# ProPrj___2025-10-18.net
KiCad netlist of a schematic drawn in EasyEDA Pro
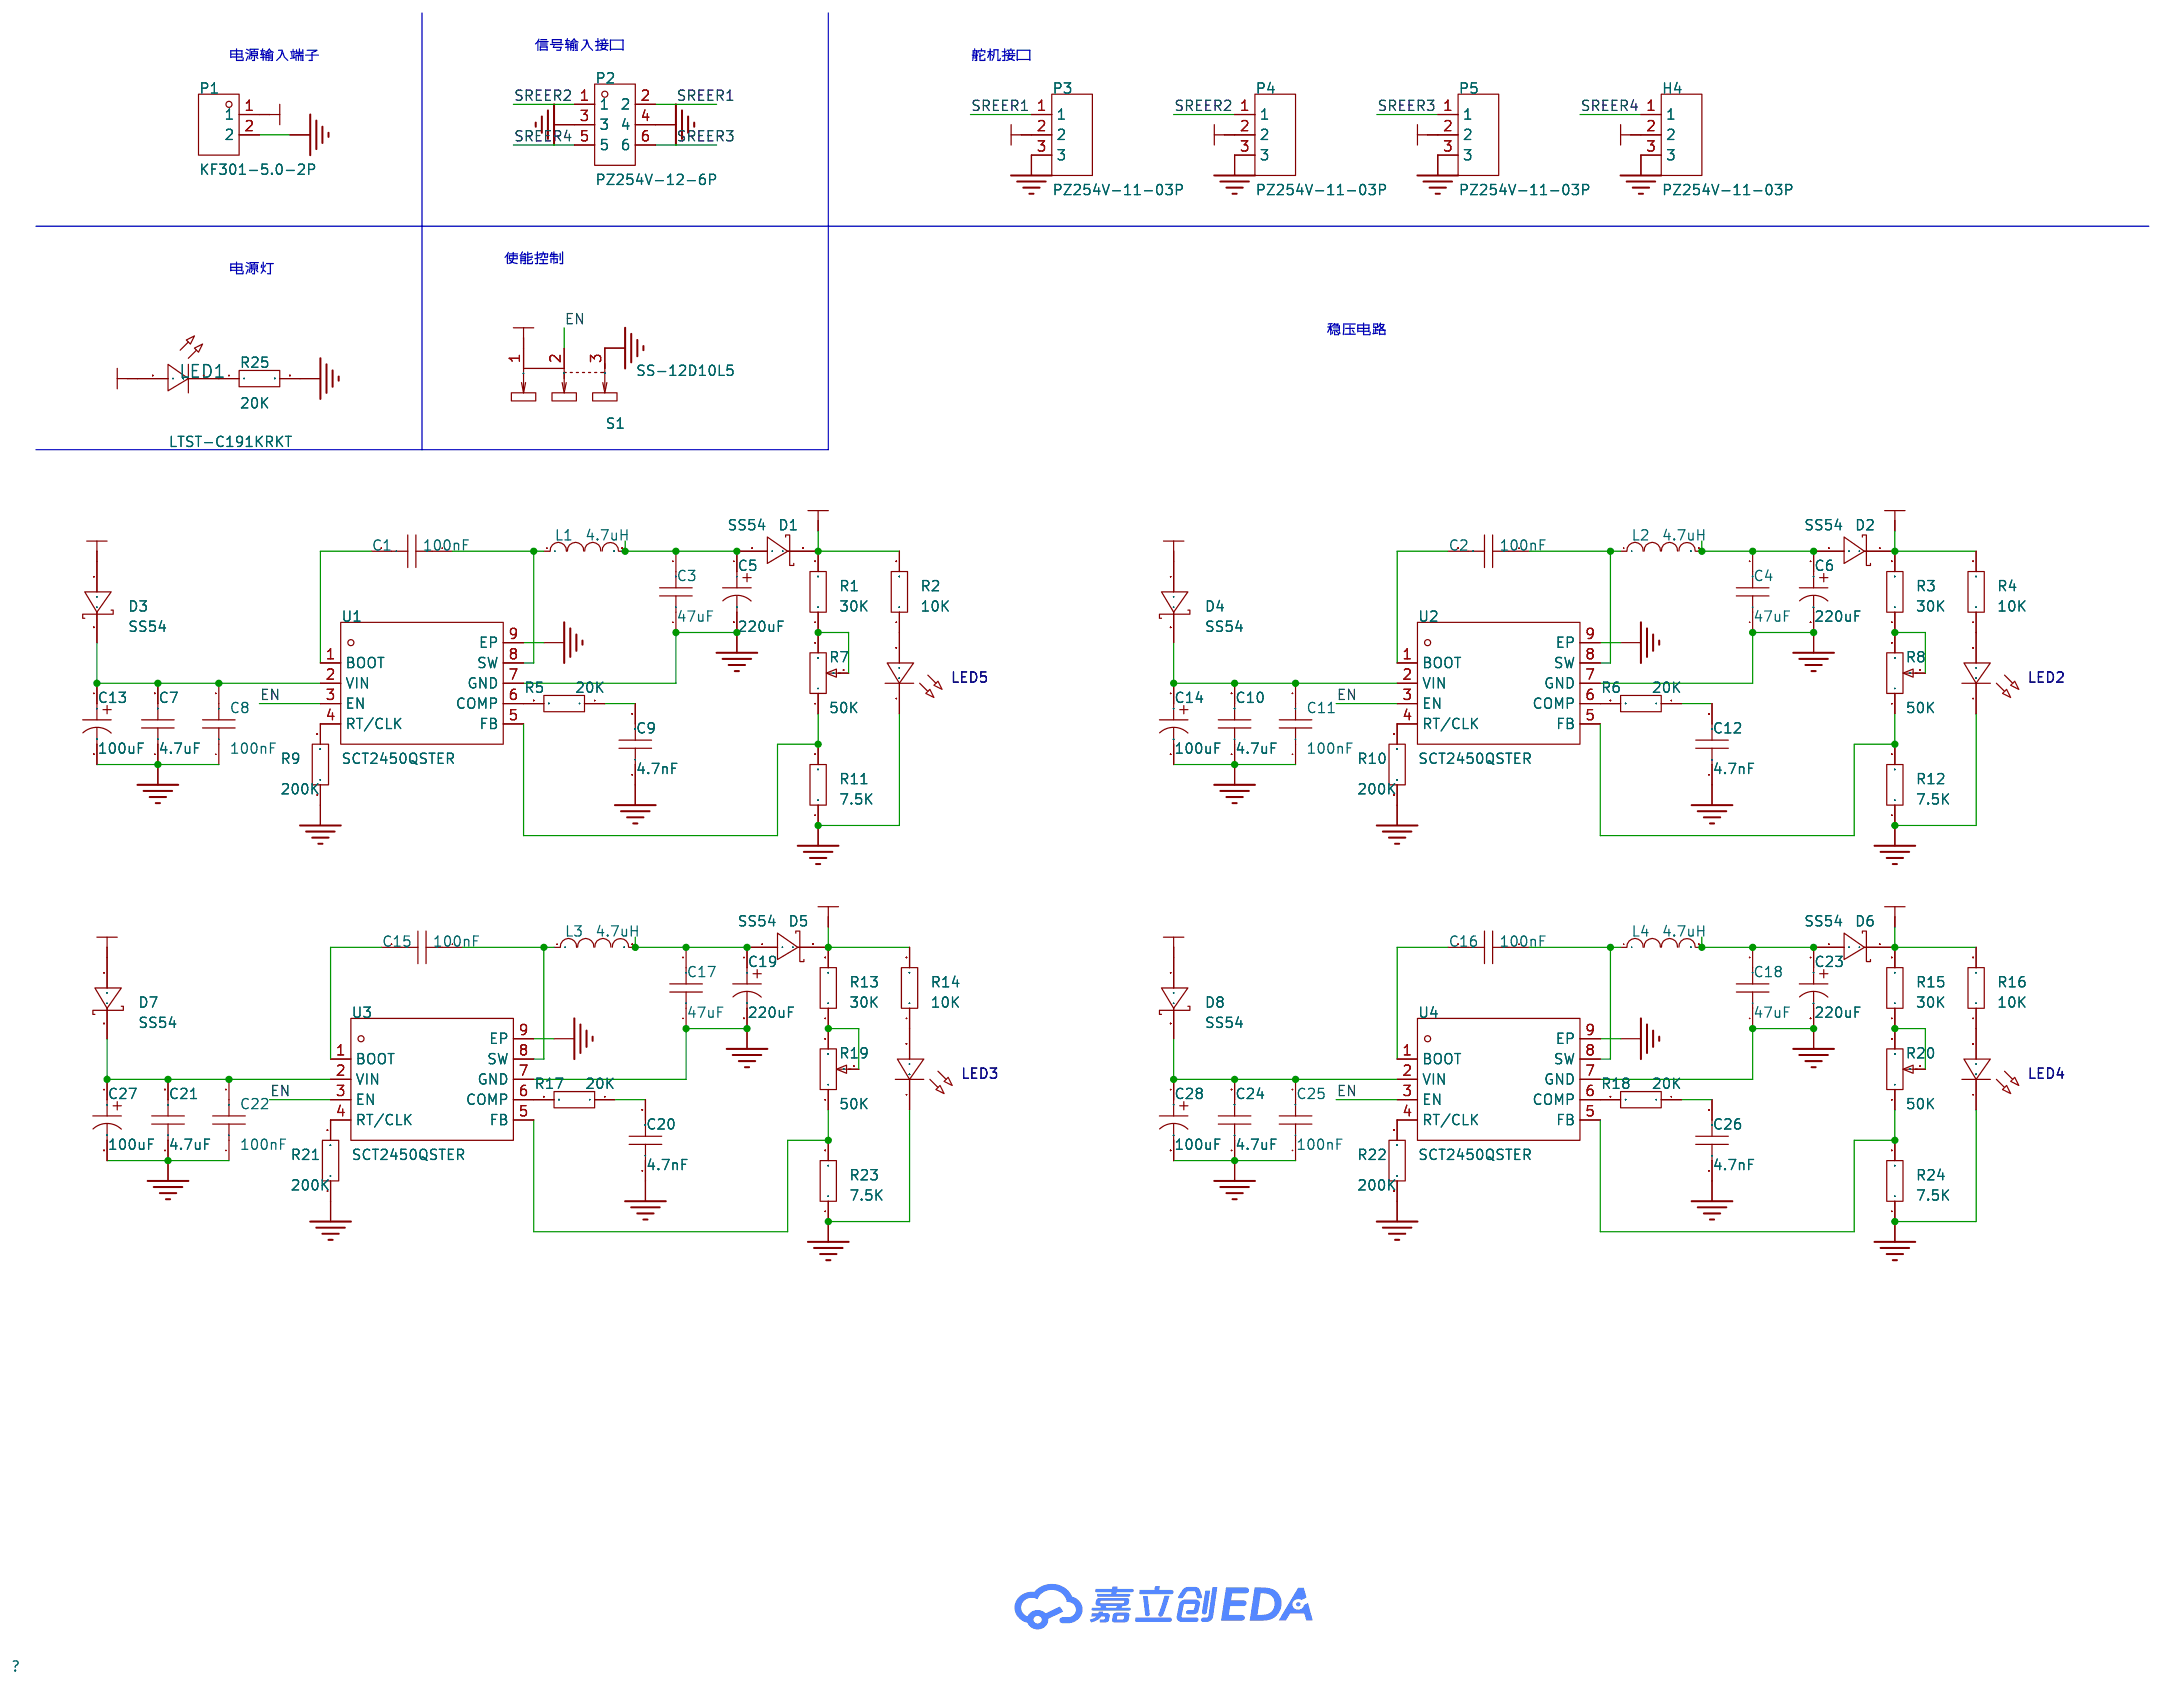
[diagram p0: schematic sheet]

(export (version "E")
  (design (tool "Eeschema 10.0.6"))
  (components
    (comp (ref "C1")
      (value "100nF")
      (footprint "easyedapro:C0603")
      (description "容值:100nF;精度:±10%;额定电压:50V;温度系数:X7R;")
      (fields
        (field (name "Manufacturer Part") "CGA0603X7R104K500JT")
        (field (name "Manufacturer") "HRE(芯声)")
      )
      (libsource (lib "easyedapro") (part "CGA0603X7R104K500JT"))
    )
    (comp (ref "C2")
      (value "100nF")
      (footprint "easyedapro:C0603")
      (description "容值:100nF;精度:±10%;额定电压:50V;温度系数:X7R;")
      (fields
        (field (name "Manufacturer Part") "CGA0603X7R104K500JT")
        (field (name "Manufacturer") "HRE(芯声)")
      )
      (libsource (lib "easyedapro") (part "CGA0603X7R104K500JT"))
    )
    (comp (ref "C3")
      (value "47uF")
      (footprint "easyedapro:C1206")
      (description "容值:47uF;精度:±20%;额定电压:25V;材质(温度系数):X5R;")
      (fields
        (field (name "Manufacturer Part") "HGC1206R5476M250NSPJ")
        (field (name "Manufacturer") "Chinocera(华瓷)")
      )
      (libsource (lib "easyedapro") (part "CGA1206X5R476M250NT"))
    )
    (comp (ref "C4")
      (value "47uF")
      (footprint "easyedapro:C1206")
      (description "容值:47uF;精度:±20%;额定电压:25V;材质(温度系数):X5R;")
      (fields
        (field (name "Manufacturer Part") "HGC1206R5476M250NSPJ")
        (field (name "Manufacturer") "Chinocera(华瓷)")
      )
      (libsource (lib "easyedapro") (part "CGA1206X5R476M250NT"))
    )
    (comp (ref "C5")
      (value "220uF")
      (footprint "easyedapro:CAP-SMD_BD6.3-L6.6-W6.6-LS7.2-FD")
      (description "容值:220uF;精度:±20%;额定电压:16V;纹波电流:110mA@120Hz;等效串联电阻:-;")
      (fields (field (name "Manufacturer Part") "FD1E221M0810") (field (name "Manufacturer") "ChengTao(诚韬)"))
      (libsource (lib "easyedapro") (part "RVT1C221M0607 220UF 16V"))
    )
    (comp (ref "C6")
      (value "220uF")
      (footprint "easyedapro:CAP-SMD_BD6.3-L6.6-W6.6-LS7.2-FD")
      (description "容值:220uF;精度:±20%;额定电压:16V;纹波电流:110mA@120Hz;等效串联电阻:-;")
      (fields (field (name "Manufacturer Part") "FD1E221M0810") (field (name "Manufacturer") "ChengTao(诚韬)"))
      (libsource (lib "easyedapro") (part "RVT1C221M0607 220UF 16V"))
    )
    (comp (ref "C7")
      (value "4.7uF")
      (footprint "easyedapro:C1206")
      (description "容值:4.7uF;精度:±10%;额定电压:35V;材质(温度系数):X5R;")
      (fields
        (field (name "Manufacturer Part") "CL31B475KBHNNNE")
        (field (name "Manufacturer") "SAMSUNG(三星)")
      )
      (libsource (lib "easyedapro") (part "CGA1206X5R475K350NT"))
    )
    (comp (ref "C8")
      (value "100nF")
      (footprint "easyedapro:C0603")
      (description "容值:100nF;精度:±10%;额定电压:50V;温度系数:X7R;")
      (fields
        (field (name "Manufacturer Part") "CGA0603X7R104K500JT")
        (field (name "Manufacturer") "HRE(芯声)")
      )
      (libsource (lib "easyedapro") (part "CGA0603X7R104K500JT"))
    )
    (comp (ref "C9")
      (value "4.7nF")
      (footprint "easyedapro:C0603")
      (description "容值:4.7nF;精度:±10%;额定电压:50V;温度系数:X7R;")
      (fields
        (field (name "Manufacturer Part") "CGA0603X7R472K500JT")
        (field (name "Manufacturer") "HRE(芯声)")
      )
      (libsource (lib "easyedapro") (part "CGA0603X7R472K500JT"))
    )
    (comp (ref "C10")
      (value "4.7uF")
      (footprint "easyedapro:C1206")
      (description "容值:4.7uF;精度:±10%;额定电压:35V;材质(温度系数):X5R;")
      (fields
        (field (name "Manufacturer Part") "CL31B475KBHNNNE")
        (field (name "Manufacturer") "SAMSUNG(三星)")
      )
      (libsource (lib "easyedapro") (part "CGA1206X5R475K350NT"))
    )
    (comp (ref "C11")
      (value "100nF")
      (footprint "easyedapro:C0603")
      (description "容值:100nF;精度:±10%;额定电压:50V;温度系数:X7R;")
      (fields
        (field (name "Manufacturer Part") "CGA0603X7R104K500JT")
        (field (name "Manufacturer") "HRE(芯声)")
      )
      (libsource (lib "easyedapro") (part "CGA0603X7R104K500JT"))
    )
    (comp (ref "C12")
      (value "4.7nF")
      (footprint "easyedapro:C0603")
      (description "容值:4.7nF;精度:±10%;额定电压:50V;温度系数:X7R;")
      (fields
        (field (name "Manufacturer Part") "CGA0603X7R472K500JT")
        (field (name "Manufacturer") "HRE(芯声)")
      )
      (libsource (lib "easyedapro") (part "CGA0603X7R472K500JT"))
    )
    (comp (ref "C13")
      (value "100uF")
      (footprint "easyedapro:CAP-SMD_BD6.3-L6.6-W6.6-LS7.3-FD")
      (description "容值:100uF;精度:±20%;额定电压:25V;纹波电流:88mA@120Hz;等效串联电阻:-;")
      (fields (field (name "Manufacturer Part") "MA25V100M6x6") (field (name "Manufacturer") "捷而瑞"))
      (libsource (lib "easyedapro") (part "RST100UF25V004"))
    )
    (comp (ref "C14")
      (value "100uF")
      (footprint "easyedapro:CAP-SMD_BD6.3-L6.6-W6.6-LS7.3-FD")
      (description "容值:100uF;精度:±20%;额定电压:25V;纹波电流:88mA@120Hz;等效串联电阻:-;")
      (fields (field (name "Manufacturer Part") "MA25V100M6x6") (field (name "Manufacturer") "捷而瑞"))
      (libsource (lib "easyedapro") (part "RST100UF25V004"))
    )
    (comp (ref "C15")
      (value "100nF")
      (footprint "easyedapro:C0603")
      (description "容值:100nF;精度:±10%;额定电压:50V;温度系数:X7R;")
      (fields
        (field (name "Manufacturer Part") "CGA0603X7R104K500JT")
        (field (name "Manufacturer") "HRE(芯声)")
      )
      (libsource (lib "easyedapro") (part "CGA0603X7R104K500JT"))
    )
    (comp (ref "C16")
      (value "100nF")
      (footprint "easyedapro:C0603")
      (description "容值:100nF;精度:±10%;额定电压:50V;温度系数:X7R;")
      (fields
        (field (name "Manufacturer Part") "CGA0603X7R104K500JT")
        (field (name "Manufacturer") "HRE(芯声)")
      )
      (libsource (lib "easyedapro") (part "CGA0603X7R104K500JT"))
    )
    (comp (ref "C17")
      (value "47uF")
      (footprint "easyedapro:C1206")
      (description "容值:47uF;精度:±20%;额定电压:25V;材质(温度系数):X5R;")
      (fields
        (field (name "Manufacturer Part") "HGC1206R5476M250NSPJ")
        (field (name "Manufacturer") "Chinocera(华瓷)")
      )
      (libsource (lib "easyedapro") (part "CGA1206X5R476M250NT"))
    )
    (comp (ref "C18")
      (value "47uF")
      (footprint "easyedapro:C1206")
      (description "容值:47uF;精度:±20%;额定电压:25V;材质(温度系数):X5R;")
      (fields
        (field (name "Manufacturer Part") "HGC1206R5476M250NSPJ")
        (field (name "Manufacturer") "Chinocera(华瓷)")
      )
      (libsource (lib "easyedapro") (part "CGA1206X5R476M250NT"))
    )
    (comp (ref "C19")
      (value "220uF")
      (footprint "easyedapro:CAP-SMD_BD6.3-L6.6-W6.6-LS7.2-FD")
      (description "容值:220uF;精度:±20%;额定电压:16V;纹波电流:110mA@120Hz;等效串联电阻:-;")
      (fields (field (name "Manufacturer Part") "FD1E221M0810") (field (name "Manufacturer") "ChengTao(诚韬)"))
      (libsource (lib "easyedapro") (part "RVT1C221M0607 220UF 16V"))
    )
    (comp (ref "C20")
      (value "4.7nF")
      (footprint "easyedapro:C0603")
      (description "容值:4.7nF;精度:±10%;额定电压:50V;温度系数:X7R;")
      (fields
        (field (name "Manufacturer Part") "CGA0603X7R472K500JT")
        (field (name "Manufacturer") "HRE(芯声)")
      )
      (libsource (lib "easyedapro") (part "CGA0603X7R472K500JT"))
    )
    (comp (ref "C21")
      (value "4.7uF")
      (footprint "easyedapro:C1206")
      (description "容值:4.7uF;精度:±10%;额定电压:35V;材质(温度系数):X5R;")
      (fields
        (field (name "Manufacturer Part") "CL31B475KBHNNNE")
        (field (name "Manufacturer") "SAMSUNG(三星)")
      )
      (libsource (lib "easyedapro") (part "CGA1206X5R475K350NT"))
    )
    (comp (ref "C22")
      (value "100nF")
      (footprint "easyedapro:C0603")
      (description "容值:100nF;精度:±10%;额定电压:50V;温度系数:X7R;")
      (fields
        (field (name "Manufacturer Part") "CGA0603X7R104K500JT")
        (field (name "Manufacturer") "HRE(芯声)")
      )
      (libsource (lib "easyedapro") (part "CGA0603X7R104K500JT"))
    )
    (comp (ref "C23")
      (value "220uF")
      (footprint "easyedapro:CAP-SMD_BD6.3-L6.6-W6.6-LS7.2-FD")
      (description "容值:220uF;精度:±20%;额定电压:16V;纹波电流:110mA@120Hz;等效串联电阻:-;")
      (fields (field (name "Manufacturer Part") "FD1E221M0810") (field (name "Manufacturer") "ChengTao(诚韬)"))
      (libsource (lib "easyedapro") (part "RVT1C221M0607 220UF 16V"))
    )
    (comp (ref "C24")
      (value "4.7uF")
      (footprint "easyedapro:C1206")
      (description "容值:4.7uF;精度:±10%;额定电压:35V;材质(温度系数):X5R;")
      (fields
        (field (name "Manufacturer Part") "CL31B475KBHNNNE")
        (field (name "Manufacturer") "SAMSUNG(三星)")
      )
      (libsource (lib "easyedapro") (part "CGA1206X5R475K350NT"))
    )
    (comp (ref "C25")
      (value "100nF")
      (footprint "easyedapro:C0603")
      (description "容值:100nF;精度:±10%;额定电压:50V;温度系数:X7R;")
      (fields
        (field (name "Manufacturer Part") "CGA0603X7R104K500JT")
        (field (name "Manufacturer") "HRE(芯声)")
      )
      (libsource (lib "easyedapro") (part "CGA0603X7R104K500JT"))
    )
    (comp (ref "C26")
      (value "4.7nF")
      (footprint "easyedapro:C0603")
      (description "容值:4.7nF;精度:±10%;额定电压:50V;温度系数:X7R;")
      (fields
        (field (name "Manufacturer Part") "CGA0603X7R472K500JT")
        (field (name "Manufacturer") "HRE(芯声)")
      )
      (libsource (lib "easyedapro") (part "CGA0603X7R472K500JT"))
    )
    (comp (ref "C27")
      (value "100uF")
      (footprint "easyedapro:CAP-SMD_BD6.3-L6.6-W6.6-LS7.3-FD")
      (description "容值:100uF;精度:±20%;额定电压:25V;纹波电流:88mA@120Hz;等效串联电阻:-;")
      (fields (field (name "Manufacturer Part") "MA25V100M6x6") (field (name "Manufacturer") "捷而瑞"))
      (libsource (lib "easyedapro") (part "RST100UF25V004"))
    )
    (comp (ref "C28")
      (value "100uF")
      (footprint "easyedapro:CAP-SMD_BD6.3-L6.6-W6.6-LS7.3-FD")
      (description "容值:100uF;精度:±20%;额定电压:25V;纹波电流:88mA@120Hz;等效串联电阻:-;")
      (fields (field (name "Manufacturer Part") "MA25V100M6x6") (field (name "Manufacturer") "捷而瑞"))
      (libsource (lib "easyedapro") (part "RST100UF25V004"))
    )
    (comp (ref "D1")
      (value "SS54")
      (footprint "easyedapro:SMA_L4.4-W2.8-LS5.4-R-RD")
      (description "二极管配置:独立式;正向压降(Vf):550mV@5A;直流反向耐压(Vr):40V;整流电流:5A;")
      (fields (field (name "Manufacturer") "MDD(辰达半导体)"))
      (libsource (lib "easyedapro") (part "SS54_C22452"))
    )
    (comp (ref "D2")
      (value "SS54")
      (footprint "easyedapro:SMA_L4.4-W2.8-LS5.4-R-RD")
      (description "二极管配置:独立式;正向压降(Vf):550mV@5A;直流反向耐压(Vr):40V;整流电流:5A;")
      (fields (field (name "Manufacturer") "MDD(辰达半导体)"))
      (libsource (lib "easyedapro") (part "SS54_C22452"))
    )
    (comp (ref "D3")
      (value "SS54")
      (footprint "easyedapro:SMA_L4.4-W2.8-LS5.4-R-RD")
      (description "二极管配置:独立式;正向压降(Vf):550mV@5A;直流反向耐压(Vr):40V;整流电流:5A;")
      (fields (field (name "Manufacturer") "MDD(辰达半导体)"))
      (libsource (lib "easyedapro") (part "SS54_C22452"))
    )
    (comp (ref "D4")
      (value "SS54")
      (footprint "easyedapro:SMA_L4.4-W2.8-LS5.4-R-RD")
      (description "二极管配置:独立式;正向压降(Vf):550mV@5A;直流反向耐压(Vr):40V;整流电流:5A;")
      (fields (field (name "Manufacturer") "MDD(辰达半导体)"))
      (libsource (lib "easyedapro") (part "SS54_C22452"))
    )
    (comp (ref "D5")
      (value "SS54")
      (footprint "easyedapro:SMA_L4.4-W2.8-LS5.4-R-RD")
      (description "二极管配置:独立式;正向压降(Vf):550mV@5A;直流反向耐压(Vr):40V;整流电流:5A;")
      (fields (field (name "Manufacturer") "MDD(辰达半导体)"))
      (libsource (lib "easyedapro") (part "SS54_C22452"))
    )
    (comp (ref "D6")
      (value "SS54")
      (footprint "easyedapro:SMA_L4.4-W2.8-LS5.4-R-RD")
      (description "二极管配置:独立式;正向压降(Vf):550mV@5A;直流反向耐压(Vr):40V;整流电流:5A;")
      (fields (field (name "Manufacturer") "MDD(辰达半导体)"))
      (libsource (lib "easyedapro") (part "SS54_C22452"))
    )
    (comp (ref "D7")
      (value "SS54")
      (footprint "easyedapro:SMA_L4.4-W2.8-LS5.4-R-RD")
      (description "二极管配置:独立式;正向压降(Vf):550mV@5A;直流反向耐压(Vr):40V;整流电流:5A;")
      (fields (field (name "Manufacturer") "MDD(辰达半导体)"))
      (libsource (lib "easyedapro") (part "SS54_C22452"))
    )
    (comp (ref "D8")
      (value "SS54")
      (footprint "easyedapro:SMA_L4.4-W2.8-LS5.4-R-RD")
      (description "二极管配置:独立式;正向压降(Vf):550mV@5A;直流反向耐压(Vr):40V;整流电流:5A;")
      (fields (field (name "Manufacturer") "MDD(辰达半导体)"))
      (libsource (lib "easyedapro") (part "SS54_C22452"))
    )
    (comp (ref "H4")
      (value "PZ254V-11-03P")
      (footprint "easyedapro:HDR-TH_3P-P2.54-V-M")
      (fields (field (name "Manufacturer") "XFCN(兴飞)"))
      (libsource (lib "easyedapro") (part "PZ254V-11-03P_C2937625"))
    )
    (comp (ref "L1")
      (value "4.7uH")
      (footprint "easyedapro:L0603")
      (fields (field (name "Manufacturer Part") "FXL0530-4R7-M") (field (name "Manufacturer") "cjiang(长江微电)"))
      (libsource (lib "easyedapro") (part "SDFL1608S100KTF"))
    )
    (comp (ref "L2")
      (value "4.7uH")
      (footprint "easyedapro:L0603")
      (fields (field (name "Manufacturer Part") "FXL0530-4R7-M") (field (name "Manufacturer") "cjiang(长江微电)"))
      (libsource (lib "easyedapro") (part "SDFL1608S100KTF"))
    )
    (comp (ref "L3")
      (value "4.7uH")
      (footprint "easyedapro:L0603")
      (fields (field (name "Manufacturer Part") "FXL0530-4R7-M") (field (name "Manufacturer") "cjiang(长江微电)"))
      (libsource (lib "easyedapro") (part "SDFL1608S100KTF"))
    )
    (comp (ref "L4")
      (value "4.7uH")
      (footprint "easyedapro:L0603")
      (fields (field (name "Manufacturer Part") "FXL0530-4R7-M") (field (name "Manufacturer") "cjiang(长江微电)"))
      (libsource (lib "easyedapro") (part "SDFL1608S100KTF"))
    )
    (comp (ref "LED1")
      (value "LTST-C191KRKT")
      (footprint "easyedapro:LED_0603")
      (fields (field (name "Manufacturer") "LITEON(光宝)"))
      (libsource (lib "easyedapro") (part "LED_R"))
    )
    (comp (ref "LED2")
      (value "~")
      (footprint "easyedapro:LED_0805")
      (libsource (lib "easyedapro") (part "LED_G"))
    )
    (comp (ref "LED3")
      (value "~")
      (footprint "easyedapro:LED_0805")
      (libsource (lib "easyedapro") (part "LED_G"))
    )
    (comp (ref "LED4")
      (value "~")
      (footprint "easyedapro:LED_0805")
      (libsource (lib "easyedapro") (part "LED_G"))
    )
    (comp (ref "LED5")
      (value "~")
      (footprint "easyedapro:LED_0805")
      (libsource (lib "easyedapro") (part "LED_G"))
    )
    (comp (ref "P1")
      (value "KF301-5.0-2P")
      (footprint "easyedapro:CONN-TH_P5.00_KF301-5.0-2P")
      (fields (field (name "Manufacturer") "KEFA(科发)"))
      (libsource (lib "easyedapro") (part "KF301-5.0-2P"))
    )
    (comp (ref "P2")
      (value "PZ254V-12-6P")
      (footprint "easyedapro:HDR-TH_6P-P2.54-V-M-R2-C3-S2.54")
      (fields (field (name "Manufacturer") "XFCN(兴飞)"))
      (libsource (lib "easyedapro") (part "PZ254V-12-6P"))
    )
    (comp (ref "P3")
      (value "PZ254V-11-03P")
      (footprint "easyedapro:HDR-TH_3P-P2.54-V-M")
      (fields (field (name "Manufacturer") "XFCN(兴飞)"))
      (libsource (lib "easyedapro") (part "PZ254V-11-03P_C2937625"))
    )
    (comp (ref "P4")
      (value "PZ254V-11-03P")
      (footprint "easyedapro:HDR-TH_3P-P2.54-V-M")
      (fields (field (name "Manufacturer") "XFCN(兴飞)"))
      (libsource (lib "easyedapro") (part "PZ254V-11-03P_C2937625"))
    )
    (comp (ref "P5")
      (value "PZ254V-11-03P")
      (footprint "easyedapro:HDR-TH_3P-P2.54-V-M")
      (fields (field (name "Manufacturer") "XFCN(兴飞)"))
      (libsource (lib "easyedapro") (part "PZ254V-11-03P_C2937625"))
    )
    (comp (ref "R1") (value "30K") (footprint "easyedapro:R0805") (libsource (lib "easyedapro") (part "电阻")))
    (comp (ref "R2") (value "10K") (footprint "easyedapro:R0805") (libsource (lib "easyedapro") (part "电阻")))
    (comp (ref "R3") (value "30K") (footprint "easyedapro:R0805") (libsource (lib "easyedapro") (part "电阻")))
    (comp (ref "R4") (value "10K") (footprint "easyedapro:R0805") (libsource (lib "easyedapro") (part "电阻")))
    (comp (ref "R5") (value "20K") (footprint "easyedapro:R0805") (libsource (lib "easyedapro") (part "电阻")))
    (comp (ref "R6") (value "20K") (footprint "easyedapro:R0805") (libsource (lib "easyedapro") (part "电阻")))
    (comp (ref "R7")
      (value "50K")
      (footprint "easyedapro:R_3386P")
      (libsource (lib "easyedapro") (part "3386P-1-103LF"))
    )
    (comp (ref "R8")
      (value "50K")
      (footprint "easyedapro:R_3386P")
      (libsource (lib "easyedapro") (part "3386P-1-103LF"))
    )
    (comp (ref "R9") (value "200K") (footprint "easyedapro:R0805") (libsource (lib "easyedapro") (part "电阻")))
    (comp (ref "R10")
      (value "200K")
      (footprint "easyedapro:R0805")
      (libsource (lib "easyedapro") (part "电阻"))
    )
    (comp (ref "R11")
      (value "7.5K")
      (footprint "easyedapro:R0805")
      (libsource (lib "easyedapro") (part "电阻"))
    )
    (comp (ref "R12")
      (value "7.5K")
      (footprint "easyedapro:R0805")
      (libsource (lib "easyedapro") (part "电阻"))
    )
    (comp (ref "R13") (value "30K") (footprint "easyedapro:R0805") (libsource (lib "easyedapro") (part "电阻")))
    (comp (ref "R14") (value "10K") (footprint "easyedapro:R0805") (libsource (lib "easyedapro") (part "电阻")))
    (comp (ref "R15") (value "30K") (footprint "easyedapro:R0805") (libsource (lib "easyedapro") (part "电阻")))
    (comp (ref "R16") (value "10K") (footprint "easyedapro:R0805") (libsource (lib "easyedapro") (part "电阻")))
    (comp (ref "R17") (value "20K") (footprint "easyedapro:R0805") (libsource (lib "easyedapro") (part "电阻")))
    (comp (ref "R18") (value "20K") (footprint "easyedapro:R0805") (libsource (lib "easyedapro") (part "电阻")))
    (comp (ref "R19")
      (value "50K")
      (footprint "easyedapro:R_3386P")
      (libsource (lib "easyedapro") (part "3386P-1-103LF"))
    )
    (comp (ref "R20")
      (value "50K")
      (footprint "easyedapro:R_3386P")
      (libsource (lib "easyedapro") (part "3386P-1-103LF"))
    )
    (comp (ref "R21")
      (value "200K")
      (footprint "easyedapro:R0805")
      (libsource (lib "easyedapro") (part "电阻"))
    )
    (comp (ref "R22")
      (value "200K")
      (footprint "easyedapro:R0805")
      (libsource (lib "easyedapro") (part "电阻"))
    )
    (comp (ref "R23")
      (value "7.5K")
      (footprint "easyedapro:R0805")
      (libsource (lib "easyedapro") (part "电阻"))
    )
    (comp (ref "R24")
      (value "7.5K")
      (footprint "easyedapro:R0805")
      (libsource (lib "easyedapro") (part "电阻"))
    )
    (comp (ref "R25") (value "20K") (footprint "easyedapro:R0805") (libsource (lib "easyedapro") (part "电阻")))
    (comp (ref "S1")
      (value "SS-12D10L5")
      (footprint "easyedapro:SW-TH_SS-12D10L5")
      (description "电路结构:单刀双掷;安装方式:直插;开关颜色:黑色;额定电流(DC):3A;额定电压(DC):125V;额定电流(AC):3A;额定电压(AC):125V;机械寿命:1万次;")
      (fields (field (name "Manufacturer") "XKB Connectivity(中国星坤)"))
      (libsource (lib "easyedapro") (part "SS-12D10L5"))
    )
    (comp (ref "U1")
      (value "SCT2450QSTER")
      (footprint "easyedapro:ESOP-8_L4.9-W3.9-P1.27-LS6.0-BL-EP")
      (description "工作电压:3.8V~36V;输出电流:5A;")
      (fields (field (name "Manufacturer") "SCT(芯洲科技)"))
      (libsource (lib "easyedapro") (part "SCT2450QSTER"))
    )
    (comp (ref "U2")
      (value "SCT2450QSTER")
      (footprint "easyedapro:ESOP-8_L4.9-W3.9-P1.27-LS6.0-BL-EP")
      (description "工作电压:3.8V~36V;输出电流:5A;")
      (fields (field (name "Manufacturer") "SCT(芯洲科技)"))
      (libsource (lib "easyedapro") (part "SCT2450QSTER"))
    )
    (comp (ref "U3")
      (value "SCT2450QSTER")
      (footprint "easyedapro:ESOP-8_L4.9-W3.9-P1.27-LS6.0-BL-EP")
      (description "工作电压:3.8V~36V;输出电流:5A;")
      (fields (field (name "Manufacturer") "SCT(芯洲科技)"))
      (libsource (lib "easyedapro") (part "SCT2450QSTER"))
    )
    (comp (ref "U4")
      (value "SCT2450QSTER")
      (footprint "easyedapro:ESOP-8_L4.9-W3.9-P1.27-LS6.0-BL-EP")
      (description "工作电压:3.8V~36V;输出电流:5A;")
      (fields (field (name "Manufacturer") "SCT(芯洲科技)"))
      (libsource (lib "easyedapro") (part "SCT2450QSTER"))
    )
  )
  (nets
    (net (code "1") (name "/EN") (class "Default")
      (node (ref "S1") (pin "2") (pinfunction "2_2") (pintype "unspecified"))
      (node (ref "U1") (pin "3") (pinfunction "EN_3") (pintype "unspecified"))
      (node (ref "U2") (pin "3") (pinfunction "EN_3") (pintype "unspecified"))
      (node (ref "U3") (pin "3") (pinfunction "EN_3") (pintype "unspecified"))
      (node (ref "U4") (pin "3") (pinfunction "EN_3") (pintype "unspecified"))
    )
    (net (code "2") (name "/SREER1") (class "Default")
      (node (ref "P2") (pin "2") (pinfunction "2_2") (pintype "unspecified"))
      (node (ref "P3") (pin "1") (pinfunction "1_1") (pintype "unspecified"))
    )
    (net (code "3") (name "/SREER2") (class "Default")
      (node (ref "P2") (pin "1") (pinfunction "1_1") (pintype "unspecified"))
      (node (ref "P4") (pin "1") (pinfunction "1_1") (pintype "unspecified"))
    )
    (net (code "4") (name "/SREER3") (class "Default")
      (node (ref "P2") (pin "6") (pinfunction "6_6") (pintype "unspecified"))
      (node (ref "P5") (pin "1") (pinfunction "1_1") (pintype "unspecified"))
    )
    (net (code "5") (name "/SREER4") (class "Default")
      (node (ref "H4") (pin "1") (pinfunction "1_1") (pintype "unspecified"))
      (node (ref "P2") (pin "5") (pinfunction "5_5") (pintype "unspecified"))
    )
    (net (code "6") (name "GND") (class "Default")
      (node (ref "C10") (pin "1") (pinfunction "1_1") (pintype "unspecified"))
      (node (ref "C11") (pin "1") (pinfunction "1_1") (pintype "unspecified"))
      (node (ref "C12") (pin "1") (pinfunction "1_1") (pintype "unspecified"))
      (node (ref "C13") (pin "2") (pinfunction "2_2") (pintype "input"))
      (node (ref "C14") (pin "2") (pinfunction "2_2") (pintype "input"))
      (node (ref "C17") (pin "1") (pinfunction "1_1") (pintype "unspecified"))
      (node (ref "C18") (pin "1") (pinfunction "1_1") (pintype "unspecified"))
      (node (ref "C19") (pin "2") (pinfunction "2_2") (pintype "input"))
      (node (ref "C20") (pin "1") (pinfunction "1_1") (pintype "unspecified"))
      (node (ref "C21") (pin "1") (pinfunction "1_1") (pintype "unspecified"))
      (node (ref "C22") (pin "1") (pinfunction "1_1") (pintype "unspecified"))
      (node (ref "C23") (pin "2") (pinfunction "2_2") (pintype "input"))
      (node (ref "C24") (pin "1") (pinfunction "1_1") (pintype "unspecified"))
      (node (ref "C25") (pin "1") (pinfunction "1_1") (pintype "unspecified"))
      (node (ref "C26") (pin "1") (pinfunction "1_1") (pintype "unspecified"))
      (node (ref "C27") (pin "2") (pinfunction "2_2") (pintype "input"))
      (node (ref "C28") (pin "2") (pinfunction "2_2") (pintype "input"))
      (node (ref "C3") (pin "1") (pinfunction "1_1") (pintype "unspecified"))
      (node (ref "C4") (pin "1") (pinfunction "1_1") (pintype "unspecified"))
      (node (ref "C5") (pin "2") (pinfunction "2_2") (pintype "input"))
      (node (ref "C6") (pin "2") (pinfunction "2_2") (pintype "input"))
      (node (ref "C7") (pin "1") (pinfunction "1_1") (pintype "unspecified"))
      (node (ref "C8") (pin "1") (pinfunction "1_1") (pintype "unspecified"))
      (node (ref "C9") (pin "1") (pinfunction "1_1") (pintype "unspecified"))
      (node (ref "H4") (pin "3") (pinfunction "3_3") (pintype "unspecified"))
      (node (ref "LED2") (pin "1") (pinfunction "C_1") (pintype "input"))
      (node (ref "LED3") (pin "1") (pinfunction "C_1") (pintype "input"))
      (node (ref "LED4") (pin "1") (pinfunction "C_1") (pintype "input"))
      (node (ref "LED5") (pin "1") (pinfunction "C_1") (pintype "input"))
      (node (ref "P1") (pin "2") (pinfunction "2_2") (pintype "unspecified"))
      (node (ref "P2") (pin "3") (pinfunction "3_3") (pintype "unspecified"))
      (node (ref "P2") (pin "4") (pinfunction "4_4") (pintype "unspecified"))
      (node (ref "P3") (pin "3") (pinfunction "3_3") (pintype "unspecified"))
      (node (ref "P4") (pin "3") (pinfunction "3_3") (pintype "unspecified"))
      (node (ref "P5") (pin "3") (pinfunction "3_3") (pintype "unspecified"))
      (node (ref "R10") (pin "1") (pinfunction "1_1") (pintype "input"))
      (node (ref "R11") (pin "1") (pinfunction "1_1") (pintype "input"))
      (node (ref "R12") (pin "1") (pinfunction "1_1") (pintype "input"))
      (node (ref "R21") (pin "1") (pinfunction "1_1") (pintype "input"))
      (node (ref "R22") (pin "1") (pinfunction "1_1") (pintype "input"))
      (node (ref "R23") (pin "1") (pinfunction "1_1") (pintype "input"))
      (node (ref "R24") (pin "1") (pinfunction "1_1") (pintype "input"))
      (node (ref "R25") (pin "2") (pinfunction "2_2") (pintype "input"))
      (node (ref "R9") (pin "1") (pinfunction "1_1") (pintype "input"))
      (node (ref "S1") (pin "3") (pinfunction "3_3") (pintype "unspecified"))
      (node (ref "U1") (pin "7") (pinfunction "GND_7") (pintype "unspecified"))
      (node (ref "U1") (pin "9") (pinfunction "EP_9") (pintype "unspecified"))
      (node (ref "U2") (pin "7") (pinfunction "GND_7") (pintype "unspecified"))
      (node (ref "U2") (pin "9") (pinfunction "EP_9") (pintype "unspecified"))
      (node (ref "U3") (pin "7") (pinfunction "GND_7") (pintype "unspecified"))
      (node (ref "U3") (pin "9") (pinfunction "EP_9") (pintype "unspecified"))
      (node (ref "U4") (pin "7") (pinfunction "GND_7") (pintype "unspecified"))
      (node (ref "U4") (pin "9") (pinfunction "EP_9") (pintype "unspecified"))
    )
    (net (code "7") (name "Net-(C9-Pad2)") (class "Default")
      (node (ref "C9") (pin "2") (pinfunction "2_2") (pintype "unspecified"))
      (node (ref "R5") (pin "1") (pinfunction "1_1") (pintype "input"))
    )
    (net (code "8") (name "Net-(C12-Pad2)") (class "Default")
      (node (ref "C12") (pin "2") (pinfunction "2_2") (pintype "unspecified"))
      (node (ref "R6") (pin "1") (pinfunction "1_1") (pintype "input"))
    )
    (net (code "9") (name "Net-(C20-Pad2)") (class "Default")
      (node (ref "C20") (pin "2") (pinfunction "2_2") (pintype "unspecified"))
      (node (ref "R17") (pin "1") (pinfunction "1_1") (pintype "input"))
    )
    (net (code "10") (name "Net-(C26-Pad2)") (class "Default")
      (node (ref "C26") (pin "2") (pinfunction "2_2") (pintype "unspecified"))
      (node (ref "R18") (pin "1") (pinfunction "1_1") (pintype "input"))
    )
    (net (code "11") (name "Net-(D1-A)") (class "Default")
      (node (ref "C3") (pin "2") (pinfunction "2_2") (pintype "unspecified"))
      (node (ref "C5") (pin "1") (pinfunction "1_1") (pintype "input"))
      (node (ref "D1") (pin "1") (pinfunction "A_1") (pintype "unspecified"))
      (node (ref "L1") (pin "2") (pinfunction "2_2") (pintype "unspecified"))
    )
    (net (code "12") (name "Net-(D2-A)") (class "Default")
      (node (ref "C4") (pin "2") (pinfunction "2_2") (pintype "unspecified"))
      (node (ref "C6") (pin "1") (pinfunction "1_1") (pintype "input"))
      (node (ref "D2") (pin "1") (pinfunction "A_1") (pintype "unspecified"))
      (node (ref "L2") (pin "2") (pinfunction "2_2") (pintype "unspecified"))
    )
    (net (code "13") (name "Net-(D3-K)") (class "Default")
      (node (ref "C13") (pin "1") (pinfunction "1_1") (pintype "input"))
      (node (ref "C7") (pin "2") (pinfunction "2_2") (pintype "unspecified"))
      (node (ref "C8") (pin "2") (pinfunction "2_2") (pintype "unspecified"))
      (node (ref "D3") (pin "2") (pinfunction "K_2") (pintype "unspecified"))
      (node (ref "U1") (pin "2") (pinfunction "VIN_2") (pintype "unspecified"))
    )
    (net (code "14") (name "Net-(D4-K)") (class "Default")
      (node (ref "C10") (pin "2") (pinfunction "2_2") (pintype "unspecified"))
      (node (ref "C11") (pin "2") (pinfunction "2_2") (pintype "unspecified"))
      (node (ref "C14") (pin "1") (pinfunction "1_1") (pintype "input"))
      (node (ref "D4") (pin "2") (pinfunction "K_2") (pintype "unspecified"))
      (node (ref "U2") (pin "2") (pinfunction "VIN_2") (pintype "unspecified"))
    )
    (net (code "15") (name "Net-(D5-A)") (class "Default")
      (node (ref "C17") (pin "2") (pinfunction "2_2") (pintype "unspecified"))
      (node (ref "C19") (pin "1") (pinfunction "1_1") (pintype "input"))
      (node (ref "D5") (pin "1") (pinfunction "A_1") (pintype "unspecified"))
      (node (ref "L3") (pin "2") (pinfunction "2_2") (pintype "unspecified"))
    )
    (net (code "16") (name "Net-(D6-A)") (class "Default")
      (node (ref "C18") (pin "2") (pinfunction "2_2") (pintype "unspecified"))
      (node (ref "C23") (pin "1") (pinfunction "1_1") (pintype "input"))
      (node (ref "D6") (pin "1") (pinfunction "A_1") (pintype "unspecified"))
      (node (ref "L4") (pin "2") (pinfunction "2_2") (pintype "unspecified"))
    )
    (net (code "17") (name "Net-(D7-K)") (class "Default")
      (node (ref "C21") (pin "2") (pinfunction "2_2") (pintype "unspecified"))
      (node (ref "C22") (pin "2") (pinfunction "2_2") (pintype "unspecified"))
      (node (ref "C27") (pin "1") (pinfunction "1_1") (pintype "input"))
      (node (ref "D7") (pin "2") (pinfunction "K_2") (pintype "unspecified"))
      (node (ref "U3") (pin "2") (pinfunction "VIN_2") (pintype "unspecified"))
    )
    (net (code "18") (name "Net-(D8-K)") (class "Default")
      (node (ref "C24") (pin "2") (pinfunction "2_2") (pintype "unspecified"))
      (node (ref "C25") (pin "2") (pinfunction "2_2") (pintype "unspecified"))
      (node (ref "C28") (pin "1") (pinfunction "1_1") (pintype "input"))
      (node (ref "D8") (pin "2") (pinfunction "K_2") (pintype "unspecified"))
      (node (ref "U4") (pin "2") (pinfunction "VIN_2") (pintype "unspecified"))
    )
    (net (code "19") (name "Net-(LED1-C)") (class "Default")
      (node (ref "LED1") (pin "1") (pinfunction "C_1") (pintype "input"))
      (node (ref "R25") (pin "1") (pinfunction "1_1") (pintype "input"))
    )
    (net (code "20") (name "Net-(LED2-A)") (class "Default")
      (node (ref "LED2") (pin "2") (pinfunction "A_2") (pintype "input"))
      (node (ref "R4") (pin "1") (pinfunction "1_1") (pintype "input"))
    )
    (net (code "21") (name "Net-(LED3-A)") (class "Default")
      (node (ref "LED3") (pin "2") (pinfunction "A_2") (pintype "input"))
      (node (ref "R14") (pin "1") (pinfunction "1_1") (pintype "input"))
    )
    (net (code "22") (name "Net-(LED4-A)") (class "Default")
      (node (ref "LED4") (pin "2") (pinfunction "A_2") (pintype "input"))
      (node (ref "R16") (pin "1") (pinfunction "1_1") (pintype "input"))
    )
    (net (code "23") (name "Net-(LED5-A)") (class "Default")
      (node (ref "LED5") (pin "2") (pinfunction "A_2") (pintype "input"))
      (node (ref "R2") (pin "1") (pinfunction "1_1") (pintype "input"))
    )
    (net (code "24") (name "Net-(R1-Pad1)") (class "Default")
      (node (ref "R1") (pin "1") (pinfunction "1_1") (pintype "input"))
      (node (ref "R7") (pin "2") (pinfunction "2_2") (pintype "input"))
      (node (ref "R7") (pin "3") (pinfunction "3_3") (pintype "input"))
    )
    (net (code "25") (name "Net-(R3-Pad1)") (class "Default")
      (node (ref "R3") (pin "1") (pinfunction "1_1") (pintype "input"))
      (node (ref "R8") (pin "2") (pinfunction "2_2") (pintype "input"))
      (node (ref "R8") (pin "3") (pinfunction "3_3") (pintype "input"))
    )
    (net (code "26") (name "Net-(R13-Pad1)") (class "Default")
      (node (ref "R13") (pin "1") (pinfunction "1_1") (pintype "input"))
      (node (ref "R19") (pin "2") (pinfunction "2_2") (pintype "input"))
      (node (ref "R19") (pin "3") (pinfunction "3_3") (pintype "input"))
    )
    (net (code "27") (name "Net-(R15-Pad1)") (class "Default")
      (node (ref "R15") (pin "1") (pinfunction "1_1") (pintype "input"))
      (node (ref "R20") (pin "2") (pinfunction "2_2") (pintype "input"))
      (node (ref "R20") (pin "3") (pinfunction "3_3") (pintype "input"))
    )
    (net (code "28") (name "Net-(U1-BOOT)") (class "Default")
      (node (ref "C1") (pin "2") (pinfunction "2_2") (pintype "unspecified"))
      (node (ref "U1") (pin "1") (pinfunction "BOOT_1") (pintype "unspecified"))
    )
    (net (code "29") (name "Net-(U1-COMP)") (class "Default")
      (node (ref "R5") (pin "2") (pinfunction "2_2") (pintype "input"))
      (node (ref "U1") (pin "6") (pinfunction "COMP_6") (pintype "unspecified"))
    )
    (net (code "30") (name "Net-(U1-FB)") (class "Default")
      (node (ref "R11") (pin "2") (pinfunction "2_2") (pintype "input"))
      (node (ref "R7") (pin "1") (pinfunction "1_1") (pintype "input"))
      (node (ref "U1") (pin "5") (pinfunction "FB_5") (pintype "unspecified"))
    )
    (net (code "31") (name "Net-(U1-RT{slash}CLK)") (class "Default")
      (node (ref "R9") (pin "2") (pinfunction "2_2") (pintype "input"))
      (node (ref "U1") (pin "4") (pinfunction "RT/CLK_4") (pintype "unspecified"))
    )
    (net (code "32") (name "Net-(U1-SW)") (class "Default")
      (node (ref "C1") (pin "1") (pinfunction "1_1") (pintype "unspecified"))
      (node (ref "L1") (pin "1") (pinfunction "1_1") (pintype "unspecified"))
      (node (ref "U1") (pin "8") (pinfunction "SW_8") (pintype "unspecified"))
    )
    (net (code "33") (name "Net-(U2-BOOT)") (class "Default")
      (node (ref "C2") (pin "2") (pinfunction "2_2") (pintype "unspecified"))
      (node (ref "U2") (pin "1") (pinfunction "BOOT_1") (pintype "unspecified"))
    )
    (net (code "34") (name "Net-(U2-COMP)") (class "Default")
      (node (ref "R6") (pin "2") (pinfunction "2_2") (pintype "input"))
      (node (ref "U2") (pin "6") (pinfunction "COMP_6") (pintype "unspecified"))
    )
    (net (code "35") (name "Net-(U2-FB)") (class "Default")
      (node (ref "R12") (pin "2") (pinfunction "2_2") (pintype "input"))
      (node (ref "R8") (pin "1") (pinfunction "1_1") (pintype "input"))
      (node (ref "U2") (pin "5") (pinfunction "FB_5") (pintype "unspecified"))
    )
    (net (code "36") (name "Net-(U2-RT{slash}CLK)") (class "Default")
      (node (ref "R10") (pin "2") (pinfunction "2_2") (pintype "input"))
      (node (ref "U2") (pin "4") (pinfunction "RT/CLK_4") (pintype "unspecified"))
    )
    (net (code "37") (name "Net-(U2-SW)") (class "Default")
      (node (ref "C2") (pin "1") (pinfunction "1_1") (pintype "unspecified"))
      (node (ref "L2") (pin "1") (pinfunction "1_1") (pintype "unspecified"))
      (node (ref "U2") (pin "8") (pinfunction "SW_8") (pintype "unspecified"))
    )
    (net (code "38") (name "Net-(U3-BOOT)") (class "Default")
      (node (ref "C15") (pin "2") (pinfunction "2_2") (pintype "unspecified"))
      (node (ref "U3") (pin "1") (pinfunction "BOOT_1") (pintype "unspecified"))
    )
    (net (code "39") (name "Net-(U3-COMP)") (class "Default")
      (node (ref "R17") (pin "2") (pinfunction "2_2") (pintype "input"))
      (node (ref "U3") (pin "6") (pinfunction "COMP_6") (pintype "unspecified"))
    )
    (net (code "40") (name "Net-(U3-FB)") (class "Default")
      (node (ref "R19") (pin "1") (pinfunction "1_1") (pintype "input"))
      (node (ref "R23") (pin "2") (pinfunction "2_2") (pintype "input"))
      (node (ref "U3") (pin "5") (pinfunction "FB_5") (pintype "unspecified"))
    )
    (net (code "41") (name "Net-(U3-RT{slash}CLK)") (class "Default")
      (node (ref "R21") (pin "2") (pinfunction "2_2") (pintype "input"))
      (node (ref "U3") (pin "4") (pinfunction "RT/CLK_4") (pintype "unspecified"))
    )
    (net (code "42") (name "Net-(U3-SW)") (class "Default")
      (node (ref "C15") (pin "1") (pinfunction "1_1") (pintype "unspecified"))
      (node (ref "L3") (pin "1") (pinfunction "1_1") (pintype "unspecified"))
      (node (ref "U3") (pin "8") (pinfunction "SW_8") (pintype "unspecified"))
    )
    (net (code "43") (name "Net-(U4-BOOT)") (class "Default")
      (node (ref "C16") (pin "2") (pinfunction "2_2") (pintype "unspecified"))
      (node (ref "U4") (pin "1") (pinfunction "BOOT_1") (pintype "unspecified"))
    )
    (net (code "44") (name "Net-(U4-COMP)") (class "Default")
      (node (ref "R18") (pin "2") (pinfunction "2_2") (pintype "input"))
      (node (ref "U4") (pin "6") (pinfunction "COMP_6") (pintype "unspecified"))
    )
    (net (code "45") (name "Net-(U4-FB)") (class "Default")
      (node (ref "R20") (pin "1") (pinfunction "1_1") (pintype "input"))
      (node (ref "R24") (pin "2") (pinfunction "2_2") (pintype "input"))
      (node (ref "U4") (pin "5") (pinfunction "FB_5") (pintype "unspecified"))
    )
    (net (code "46") (name "Net-(U4-RT{slash}CLK)") (class "Default")
      (node (ref "R22") (pin "2") (pinfunction "2_2") (pintype "input"))
      (node (ref "U4") (pin "4") (pinfunction "RT/CLK_4") (pintype "unspecified"))
    )
    (net (code "47") (name "Net-(U4-SW)") (class "Default")
      (node (ref "C16") (pin "1") (pinfunction "1_1") (pintype "unspecified"))
      (node (ref "L4") (pin "1") (pinfunction "1_1") (pintype "unspecified"))
      (node (ref "U4") (pin "8") (pinfunction "SW_8") (pintype "unspecified"))
    )
    (net (code "48") (name "VCCSREER1") (class "Default")
      (node (ref "D1") (pin "2") (pinfunction "K_2") (pintype "unspecified"))
      (node (ref "P3") (pin "2") (pinfunction "2_2") (pintype "unspecified"))
      (node (ref "R1") (pin "2") (pinfunction "2_2") (pintype "input"))
      (node (ref "R2") (pin "2") (pinfunction "2_2") (pintype "input"))
    )
    (net (code "49") (name "VCCSREER2") (class "Default")
      (node (ref "D2") (pin "2") (pinfunction "K_2") (pintype "unspecified"))
      (node (ref "P4") (pin "2") (pinfunction "2_2") (pintype "unspecified"))
      (node (ref "R3") (pin "2") (pinfunction "2_2") (pintype "input"))
      (node (ref "R4") (pin "2") (pinfunction "2_2") (pintype "input"))
    )
    (net (code "50") (name "VCCSREER3") (class "Default")
      (node (ref "D5") (pin "2") (pinfunction "K_2") (pintype "unspecified"))
      (node (ref "P5") (pin "2") (pinfunction "2_2") (pintype "unspecified"))
      (node (ref "R13") (pin "2") (pinfunction "2_2") (pintype "input"))
      (node (ref "R14") (pin "2") (pinfunction "2_2") (pintype "input"))
    )
    (net (code "51") (name "VCCSREER4") (class "Default")
      (node (ref "D6") (pin "2") (pinfunction "K_2") (pintype "unspecified"))
      (node (ref "H4") (pin "2") (pinfunction "2_2") (pintype "unspecified"))
      (node (ref "R15") (pin "2") (pinfunction "2_2") (pintype "input"))
      (node (ref "R16") (pin "2") (pinfunction "2_2") (pintype "input"))
    )
    (net (code "52") (name "VIN") (class "Default")
      (node (ref "D3") (pin "1") (pinfunction "A_1") (pintype "unspecified"))
      (node (ref "D4") (pin "1") (pinfunction "A_1") (pintype "unspecified"))
      (node (ref "D7") (pin "1") (pinfunction "A_1") (pintype "unspecified"))
      (node (ref "D8") (pin "1") (pinfunction "A_1") (pintype "unspecified"))
      (node (ref "LED1") (pin "2") (pinfunction "A_2") (pintype "input"))
      (node (ref "P1") (pin "1") (pinfunction "1_1") (pintype "unspecified"))
      (node (ref "S1") (pin "1") (pinfunction "1_1") (pintype "unspecified"))
    )
  )
)
